# Esquematico.net
KiCad netlist of a schematic drawn in Altium Designer
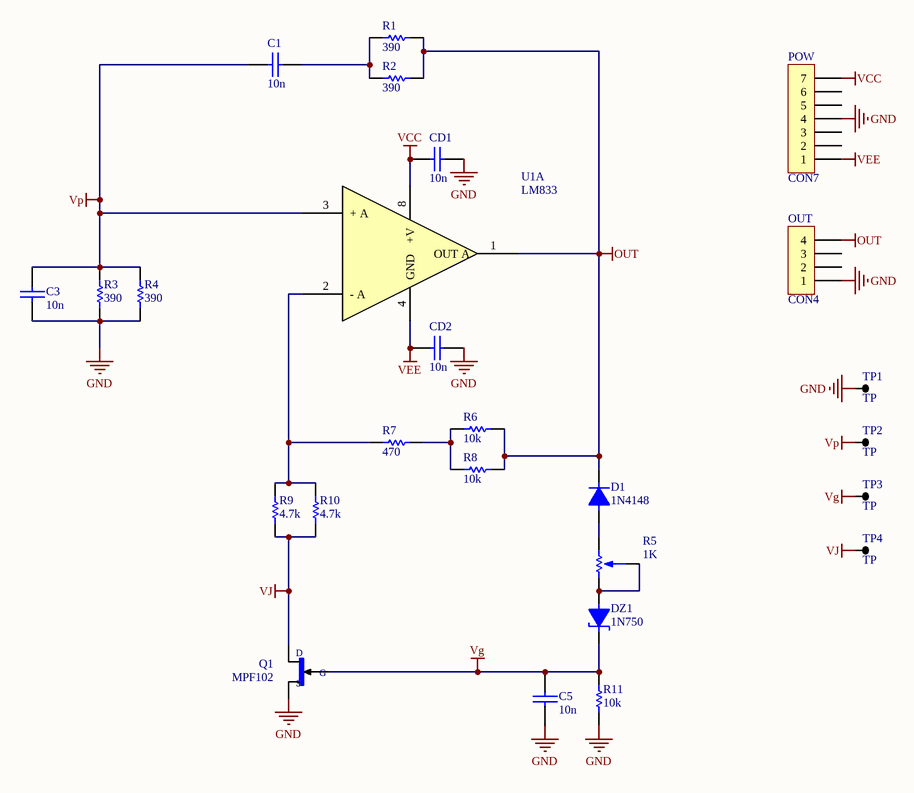
[diagram p0: Esquematico.SchDoc]

(export (version "E")
  (design (tool "Eeschema 10.0.6"))
  (components
    (comp (ref "C1") (value "10n") (footprint "CAP200") (libsource (lib "LIBEBAL") (part "CAP")))
    (comp (ref "C3") (value "10n") (footprint "CAP200") (libsource (lib "LIBEBAL") (part "CAP")))
    (comp (ref "C5") (value "10n") (footprint "CAP200") (libsource (lib "LIBEBAL") (part "CAP")))
    (comp (ref "CD1") (value "10n") (footprint "CAP200") (libsource (lib "LIBEBAL") (part "CAP")))
    (comp (ref "CD2") (value "10n") (footprint "CAP200") (libsource (lib "LIBEBAL") (part "CAP")))
    (comp (ref "D1") (value "1N4148") (footprint "DO41") (libsource (lib "LIBEBAL") (part "DIODO")))
    (comp (ref "DZ1") (value "1N750") (footprint "DO41") (libsource (lib "LIBEBAL") (part "DIODO ZENER")))
    (comp (ref "OUT") (value "CON4") (footprint "SIP4") (libsource (lib "LIBEBAL") (part "CON4")))
    (comp (ref "POW") (value "CON7") (footprint "SIP7") (libsource (lib "LIBEBAL") (part "CON7")))
    (comp (ref "Q1")
      (value "MPF102")
      (footprint "*TO92F")
      (description "JFET 25V 10mA")
      (fields (field (name "MF") "ON Semiconductor"))
      (libsource (lib "MPF102") (part "MPF102"))
    )
    (comp (ref "R1") (value "390") (footprint "0805") (libsource (lib "LIBEBAL") (part "RES")))
    (comp (ref "R2") (value "390") (footprint "0805") (libsource (lib "LIBEBAL") (part "RES")))
    (comp (ref "R3") (value "390") (footprint "0805") (libsource (lib "LIBEBAL") (part "RES")))
    (comp (ref "R4") (value "390") (footprint "0805") (libsource (lib "LIBEBAL") (part "RES")))
    (comp (ref "R5") (value "1K") (footprint "PRESET V") (libsource (lib "LIBEBAL") (part "PRESET")))
    (comp (ref "R6") (value "10k") (footprint "0805") (libsource (lib "LIBEBAL") (part "RES")))
    (comp (ref "R7") (value "470") (footprint "0805") (libsource (lib "LIBEBAL") (part "RES")))
    (comp (ref "R8") (value "10k") (footprint "0805") (libsource (lib "LIBEBAL") (part "RES")))
    (comp (ref "R9") (value "4.7k") (footprint "0805") (libsource (lib "LIBEBAL") (part "RES")))
    (comp (ref "R10") (value "4.7k") (footprint "0805") (libsource (lib "LIBEBAL") (part "RES")))
    (comp (ref "R11") (value "10k") (footprint "0805") (libsource (lib "LIBEBAL") (part "RES")))
    (comp (ref "TP1") (value "TP") (footprint "TPTH") (libsource (lib "LIBEBAL") (part "TP")))
    (comp (ref "TP2") (value "TP") (footprint "TPTH") (libsource (lib "LIBEBAL") (part "TP")))
    (comp (ref "TP3") (value "TP") (footprint "TPTH") (libsource (lib "LIBEBAL") (part "TP")))
    (comp (ref "TP4") (value "TP") (footprint "TPTH") (libsource (lib "LIBEBAL") (part "TP")))
    (comp (ref "U1")
      (value "LM833")
      (footprint "DIP8")
      (description "Dual Audio Operational Amplifier")
      (libsource (lib "LIBEBAL") (part "LM833"))
    )
  )
  (nets
    (net (code "1") (name "GND") (class "Default")
      (node (ref "C3") (pin "2") (pinfunction "2_2") (pintype "passive"))
      (node (ref "C5") (pin "1") (pinfunction "1_1") (pintype "passive"))
      (node (ref "CD1") (pin "2") (pinfunction "2_2") (pintype "passive"))
      (node (ref "CD2") (pin "2") (pinfunction "2_2") (pintype "passive"))
      (node (ref "OUT") (pin "1") (pinfunction "1_1") (pintype "passive"))
      (node (ref "POW") (pin "4") (pinfunction "4_4") (pintype "passive"))
      (node (ref "Q1") (pin "2") (pinfunction "S_2") (pintype "passive"))
      (node (ref "R11") (pin "1") (pinfunction "1_1") (pintype "passive"))
      (node (ref "R3") (pin "1") (pinfunction "1_1") (pintype "passive"))
      (node (ref "R4") (pin "1") (pinfunction "1_1") (pintype "passive"))
      (node (ref "TP1") (pin "1") (pinfunction "1_1") (pintype "passive"))
    )
    (net (code "2") (name "Net-(C1-Pad2)") (class "Default")
      (node (ref "C1") (pin "2") (pinfunction "2_2") (pintype "passive"))
      (node (ref "R1") (pin "2") (pinfunction "2_2") (pintype "passive"))
      (node (ref "R2") (pin "2") (pinfunction "2_2") (pintype "passive"))
    )
    (net (code "3") (name "Net-(D1-Pad1)") (class "Default")
      (node (ref "D1") (pin "1") (pinfunction "1_1") (pintype "passive"))
      (node (ref "R5") (pin "1") (pinfunction "1_1") (pintype "passive"))
    )
    (net (code "4") (name "Net-(DZ1-Pad1)") (class "Default")
      (node (ref "DZ1") (pin "1") (pinfunction "1_1") (pintype "passive"))
      (node (ref "R5") (pin "2") (pinfunction "2_2") (pintype "passive"))
      (node (ref "R5") (pin "3") (pinfunction "3_3") (pintype "passive"))
    )
    (net (code "5") (name "Net-(R6-Pad2)") (class "Default")
      (node (ref "R6") (pin "2") (pinfunction "2_2") (pintype "passive"))
      (node (ref "R7") (pin "1") (pinfunction "1_1") (pintype "passive"))
      (node (ref "R8") (pin "2") (pinfunction "2_2") (pintype "passive"))
    )
    (net (code "6") (name "Net-(U1A--_A)") (class "Default")
      (node (ref "R10") (pin "2") (pinfunction "2_2") (pintype "passive"))
      (node (ref "R7") (pin "2") (pinfunction "2_2") (pintype "passive"))
      (node (ref "R9") (pin "2") (pinfunction "2_2") (pintype "passive"))
      (node (ref "U1") (pin "2") (pinfunction "-_A_2") (pintype "passive"))
    )
    (net (code "7") (name "OUT") (class "Default")
      (node (ref "D1") (pin "2") (pinfunction "2_2") (pintype "passive"))
      (node (ref "OUT") (pin "4") (pinfunction "4_4") (pintype "passive"))
      (node (ref "R1") (pin "1") (pinfunction "1_1") (pintype "passive"))
      (node (ref "R2") (pin "1") (pinfunction "1_1") (pintype "passive"))
      (node (ref "R6") (pin "1") (pinfunction "1_1") (pintype "passive"))
      (node (ref "R8") (pin "1") (pinfunction "1_1") (pintype "passive"))
      (node (ref "U1") (pin "1") (pinfunction "OUT_A_1") (pintype "passive"))
    )
    (net (code "8") (name "VCC") (class "Default")
      (node (ref "CD1") (pin "1") (pinfunction "1_1") (pintype "passive"))
      (node (ref "POW") (pin "7") (pinfunction "7_7") (pintype "passive"))
      (node (ref "U1") (pin "8") (pinfunction "+V_8") (pintype "passive"))
    )
    (net (code "9") (name "VEE") (class "Default")
      (node (ref "CD2") (pin "1") (pinfunction "1_1") (pintype "passive"))
      (node (ref "POW") (pin "1") (pinfunction "1_1") (pintype "passive"))
      (node (ref "U1") (pin "4") (pinfunction "GND_4") (pintype "passive"))
    )
    (net (code "10") (name "VJ") (class "Default")
      (node (ref "Q1") (pin "1") (pinfunction "D_1") (pintype "passive"))
      (node (ref "R10") (pin "1") (pinfunction "1_1") (pintype "passive"))
      (node (ref "R9") (pin "1") (pinfunction "1_1") (pintype "passive"))
      (node (ref "TP4") (pin "1") (pinfunction "1_1") (pintype "passive"))
    )
    (net (code "11") (name "Vg") (class "Default")
      (node (ref "C5") (pin "2") (pinfunction "2_2") (pintype "passive"))
      (node (ref "DZ1") (pin "2") (pinfunction "2_2") (pintype "passive"))
      (node (ref "Q1") (pin "3") (pinfunction "G_3") (pintype "passive"))
      (node (ref "R11") (pin "2") (pinfunction "2_2") (pintype "passive"))
      (node (ref "TP3") (pin "1") (pinfunction "1_1") (pintype "passive"))
    )
    (net (code "12") (name "Vp") (class "Default")
      (node (ref "C1") (pin "1") (pinfunction "1_1") (pintype "passive"))
      (node (ref "C3") (pin "1") (pinfunction "1_1") (pintype "passive"))
      (node (ref "R3") (pin "2") (pinfunction "2_2") (pintype "passive"))
      (node (ref "R4") (pin "2") (pinfunction "2_2") (pintype "passive"))
      (node (ref "TP2") (pin "1") (pinfunction "1_1") (pintype "passive"))
      (node (ref "U1") (pin "3") (pinfunction "+_A_3") (pintype "passive"))
    )
    (net (code "13") (name "unconnected-(OUT-Pad2)") (class "Default")
      (node (ref "OUT") (pin "2") (pinfunction "2_2") (pintype "passive"))
    )
    (net (code "14") (name "unconnected-(OUT-Pad3)") (class "Default")
      (node (ref "OUT") (pin "3") (pinfunction "3_3") (pintype "passive"))
    )
    (net (code "15") (name "unconnected-(POW-Pad2)") (class "Default")
      (node (ref "POW") (pin "2") (pinfunction "2_2") (pintype "passive"))
    )
    (net (code "16") (name "unconnected-(POW-Pad3)") (class "Default")
      (node (ref "POW") (pin "3") (pinfunction "3_3") (pintype "passive"))
    )
    (net (code "17") (name "unconnected-(POW-Pad5)") (class "Default")
      (node (ref "POW") (pin "5") (pinfunction "5_5") (pintype "passive"))
    )
    (net (code "18") (name "unconnected-(POW-Pad6)") (class "Default")
      (node (ref "POW") (pin "6") (pinfunction "6_6") (pintype "passive"))
    )
  )
)
